# Teensy-Futurlec-Shield_v2.net
KiCad netlist of a schematic drawn in EAGLE
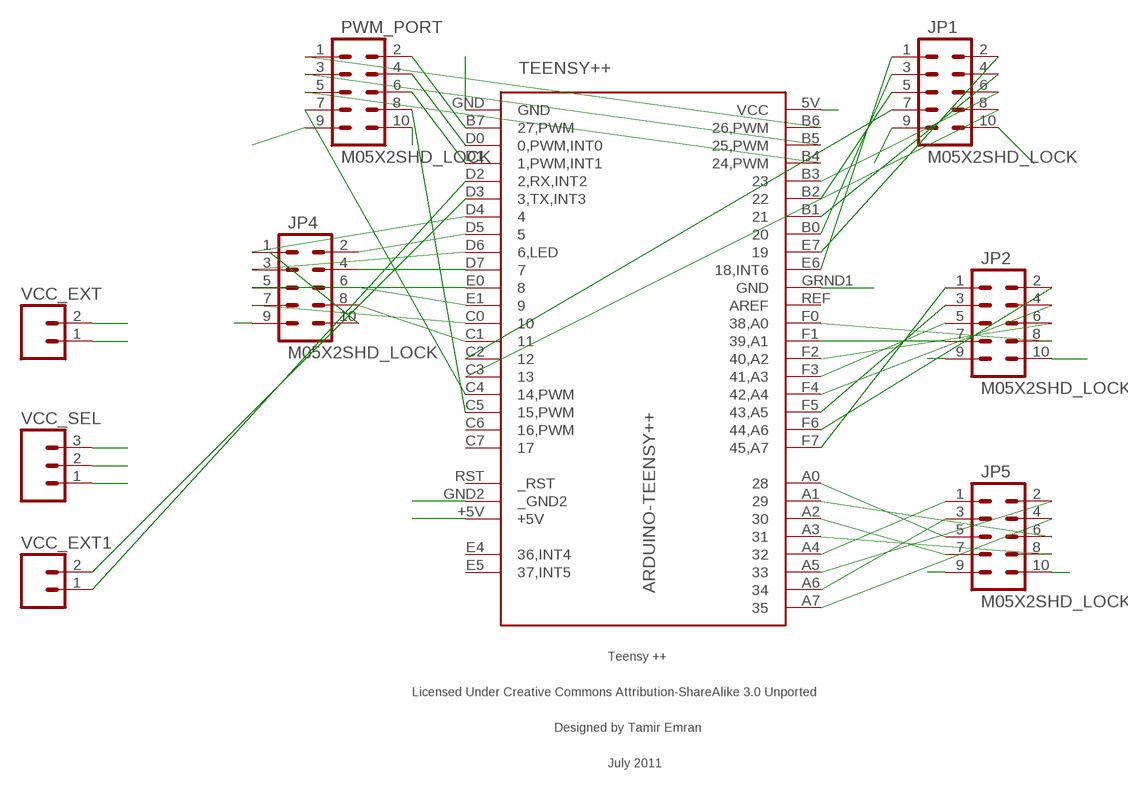
[diagram p0: schematic, sheet 1]

(export (version "E")
  (design (tool "Eeschema 10.0.6"))
  (components
    (comp (ref "JP1")
      (value "M05X2SHD_LOCK")
      (footprint "eagle-import:2X5-SHROUDED_LOCK")
      (libsource (lib "eagle-import") (part "M05X2SHD_LOCK"))
    )
    (comp (ref "JP2")
      (value "M05X2SHD_LOCK")
      (footprint "eagle-import:2X5-SHROUDED_LOCK")
      (libsource (lib "eagle-import") (part "M05X2SHD_LOCK"))
    )
    (comp (ref "JP4")
      (value "M05X2SHD_LOCK")
      (footprint "eagle-import:2X5-SHROUDED_LOCK")
      (libsource (lib "eagle-import") (part "M05X2SHD_LOCK"))
    )
    (comp (ref "JP5")
      (value "M05X2SHD_LOCK")
      (footprint "eagle-import:2X5-SHROUDED_LOCK")
      (libsource (lib "eagle-import") (part "M05X2SHD_LOCK"))
    )
    (comp (ref "PWM_PORT")
      (value "M05X2SHD_LOCK")
      (footprint "eagle-import:2X5-SHROUDED_LOCK")
      (libsource (lib "eagle-import") (part "M05X2SHD_LOCK"))
    )
    (comp (ref "TEENSY++")
      (value "ARDUINO-TEENSY++")
      (footprint "eagle-import:TEENSY++")
      (libsource (lib "eagle-import") (part "ARDUINO-TEENSY++"))
    )
    (comp (ref "VCC_EXT")
      (value "M02POLAR_LOCK")
      (footprint "eagle-import:MOLEX-1X2_LOCK")
      (libsource (lib "eagle-import") (part "M02POLAR_LOCK"))
    )
    (comp (ref "VCC_EXT1")
      (value "M02POLAR_LOCK")
      (footprint "eagle-import:MOLEX-1X2_LOCK")
      (libsource (lib "eagle-import") (part "M02POLAR_LOCK"))
    )
    (comp (ref "VCC_SEL")
      (value "M03PTH")
      (footprint "eagle-import:1X03")
      (libsource (lib "eagle-import") (part "M03PTH"))
    )
  )
  (nets
    (net (code "1") (name "/GND") (class "Default")
      (node (ref "JP1") (pin "10") (pinfunction "10_10") (pintype "passive"))
      (node (ref "JP2") (pin "10") (pinfunction "10_10") (pintype "passive"))
      (node (ref "JP4") (pin "10") (pinfunction "10_10") (pintype "passive"))
      (node (ref "JP5") (pin "10") (pinfunction "10_10") (pintype "passive"))
      (node (ref "PWM_PORT") (pin "10") (pinfunction "10_10") (pintype "passive"))
      (node (ref "TEENSY++") (pin "GND") (pinfunction "GND_GND") (pintype "power_in"))
      (node (ref "TEENSY++") (pin "GND2") (pinfunction "_GND2_GND2") (pintype "power_in"))
      (node (ref "TEENSY++") (pin "GRND1") (pinfunction "GND_GRND1") (pintype "power_in"))
      (node (ref "VCC_EXT") (pin "2") (pinfunction "2_2") (pintype "passive"))
    )
    (net (code "2") (name "/VCC") (class "Default")
      (node (ref "JP1") (pin "9") (pinfunction "9_9") (pintype "passive"))
      (node (ref "JP2") (pin "9") (pinfunction "9_9") (pintype "passive"))
      (node (ref "JP4") (pin "9") (pinfunction "9_9") (pintype "passive"))
      (node (ref "JP5") (pin "9") (pinfunction "9_9") (pintype "passive"))
      (node (ref "PWM_PORT") (pin "9") (pinfunction "9_9") (pintype "passive"))
      (node (ref "VCC_SEL") (pin "2") (pinfunction "2_2") (pintype "passive"))
    )
    (net (code "3") (name "/VCC_EXT") (class "Default")
      (node (ref "VCC_EXT") (pin "1") (pinfunction "1_1") (pintype "passive"))
      (node (ref "VCC_SEL") (pin "3") (pinfunction "3_3") (pintype "passive"))
    )
    (net (code "4") (name "/VCC_TEENSY") (class "Default")
      (node (ref "TEENSY++") (pin "+5V") (pinfunction "+5V_+5V") (pintype "power_in"))
      (node (ref "TEENSY++") (pin "5V") (pinfunction "VCC_5V") (pintype "power_in"))
      (node (ref "VCC_SEL") (pin "1") (pinfunction "1_1") (pintype "passive"))
    )
    (net (code "5") (name "Net-(TEENSY++-0,PWM,INT0)") (class "Default")
      (node (ref "PWM_PORT") (pin "4") (pinfunction "4_4") (pintype "passive"))
      (node (ref "TEENSY++") (pin "D0") (pinfunction "0,PWM,INT0_D0") (pintype "bidirectional"))
    )
    (net (code "6") (name "Net-(TEENSY++-1,PWM,INT1)") (class "Default")
      (node (ref "PWM_PORT") (pin "6") (pinfunction "6_6") (pintype "passive"))
      (node (ref "TEENSY++") (pin "D1") (pinfunction "1,PWM,INT1_D1") (pintype "bidirectional"))
    )
    (net (code "7") (name "Net-(TEENSY++-2,RX,INT2)") (class "Default")
      (node (ref "TEENSY++") (pin "D2") (pinfunction "2,RX,INT2_D2") (pintype "bidirectional"))
      (node (ref "VCC_EXT1") (pin "1") (pinfunction "1_1") (pintype "passive"))
    )
    (net (code "8") (name "Net-(TEENSY++-3,TX,INT3)") (class "Default")
      (node (ref "TEENSY++") (pin "D3") (pinfunction "3,TX,INT3_D3") (pintype "bidirectional"))
      (node (ref "VCC_EXT1") (pin "2") (pinfunction "2_2") (pintype "passive"))
    )
    (net (code "9") (name "Net-(TEENSY++-4)") (class "Default")
      (node (ref "JP4") (pin "1") (pinfunction "1_1") (pintype "passive"))
      (node (ref "TEENSY++") (pin "D4") (pinfunction "4_D4") (pintype "bidirectional"))
    )
    (net (code "10") (name "Net-(TEENSY++-5)") (class "Default")
      (node (ref "JP4") (pin "2") (pinfunction "2_2") (pintype "passive"))
      (node (ref "TEENSY++") (pin "D5") (pinfunction "5_D5") (pintype "bidirectional"))
    )
    (net (code "11") (name "Net-(TEENSY++-6,LED)") (class "Default")
      (node (ref "JP4") (pin "3") (pinfunction "3_3") (pintype "passive"))
      (node (ref "TEENSY++") (pin "D6") (pinfunction "6,LED_D6") (pintype "bidirectional"))
    )
    (net (code "12") (name "Net-(TEENSY++-7)") (class "Default")
      (node (ref "JP4") (pin "4") (pinfunction "4_4") (pintype "passive"))
      (node (ref "TEENSY++") (pin "D7") (pinfunction "7_D7") (pintype "bidirectional"))
    )
    (net (code "13") (name "Net-(TEENSY++-8)") (class "Default")
      (node (ref "JP4") (pin "5") (pinfunction "5_5") (pintype "passive"))
      (node (ref "TEENSY++") (pin "E0") (pinfunction "8_E0") (pintype "bidirectional"))
    )
    (net (code "14") (name "Net-(TEENSY++-9)") (class "Default")
      (node (ref "JP4") (pin "6") (pinfunction "6_6") (pintype "passive"))
      (node (ref "TEENSY++") (pin "E1") (pinfunction "9_E1") (pintype "bidirectional"))
    )
    (net (code "15") (name "Net-(TEENSY++-10)") (class "Default")
      (node (ref "JP4") (pin "7") (pinfunction "7_7") (pintype "passive"))
      (node (ref "TEENSY++") (pin "C0") (pinfunction "10_C0") (pintype "bidirectional"))
    )
    (net (code "16") (name "Net-(TEENSY++-11)") (class "Default")
      (node (ref "JP4") (pin "8") (pinfunction "8_8") (pintype "passive"))
      (node (ref "TEENSY++") (pin "C1") (pinfunction "11_C1") (pintype "bidirectional"))
    )
    (net (code "17") (name "Net-(TEENSY++-12)") (class "Default")
      (node (ref "JP1") (pin "7") (pinfunction "7_7") (pintype "passive"))
      (node (ref "TEENSY++") (pin "C2") (pinfunction "12_C2") (pintype "bidirectional"))
    )
    (net (code "18") (name "Net-(TEENSY++-13)") (class "Default")
      (node (ref "JP1") (pin "8") (pinfunction "8_8") (pintype "passive"))
      (node (ref "TEENSY++") (pin "C3") (pinfunction "13_C3") (pintype "bidirectional"))
    )
    (net (code "19") (name "Net-(TEENSY++-14,PWM)") (class "Default")
      (node (ref "PWM_PORT") (pin "7") (pinfunction "7_7") (pintype "passive"))
      (node (ref "TEENSY++") (pin "C4") (pinfunction "14,PWM_C4") (pintype "bidirectional"))
    )
    (net (code "20") (name "Net-(TEENSY++-15,PWM)") (class "Default")
      (node (ref "PWM_PORT") (pin "8") (pinfunction "8_8") (pintype "passive"))
      (node (ref "TEENSY++") (pin "C5") (pinfunction "15,PWM_C5") (pintype "bidirectional"))
    )
    (net (code "21") (name "Net-(TEENSY++-18,INT6)") (class "Default")
      (node (ref "JP1") (pin "1") (pinfunction "1_1") (pintype "passive"))
      (node (ref "TEENSY++") (pin "E6") (pinfunction "18,INT6_E6") (pintype "bidirectional"))
    )
    (net (code "22") (name "Net-(TEENSY++-19)") (class "Default")
      (node (ref "JP1") (pin "2") (pinfunction "2_2") (pintype "passive"))
      (node (ref "TEENSY++") (pin "E7") (pinfunction "19_E7") (pintype "bidirectional"))
    )
    (net (code "23") (name "Net-(TEENSY++-20)") (class "Default")
      (node (ref "JP1") (pin "3") (pinfunction "3_3") (pintype "passive"))
      (node (ref "TEENSY++") (pin "B0") (pinfunction "20_B0") (pintype "bidirectional"))
    )
    (net (code "24") (name "Net-(TEENSY++-21)") (class "Default")
      (node (ref "JP1") (pin "4") (pinfunction "4_4") (pintype "passive"))
      (node (ref "TEENSY++") (pin "B1") (pinfunction "21_B1") (pintype "bidirectional"))
    )
    (net (code "25") (name "Net-(TEENSY++-22)") (class "Default")
      (node (ref "JP1") (pin "5") (pinfunction "5_5") (pintype "passive"))
      (node (ref "TEENSY++") (pin "B2") (pinfunction "22_B2") (pintype "bidirectional"))
    )
    (net (code "26") (name "Net-(TEENSY++-23)") (class "Default")
      (node (ref "JP1") (pin "6") (pinfunction "6_6") (pintype "passive"))
      (node (ref "TEENSY++") (pin "B3") (pinfunction "23_B3") (pintype "bidirectional"))
    )
    (net (code "27") (name "Net-(TEENSY++-24,PWM)") (class "Default")
      (node (ref "PWM_PORT") (pin "5") (pinfunction "5_5") (pintype "passive"))
      (node (ref "TEENSY++") (pin "B4") (pinfunction "24,PWM_B4") (pintype "bidirectional"))
    )
    (net (code "28") (name "Net-(TEENSY++-25,PWM)") (class "Default")
      (node (ref "PWM_PORT") (pin "3") (pinfunction "3_3") (pintype "passive"))
      (node (ref "TEENSY++") (pin "B5") (pinfunction "25,PWM_B5") (pintype "bidirectional"))
    )
    (net (code "29") (name "Net-(TEENSY++-26,PWM)") (class "Default")
      (node (ref "PWM_PORT") (pin "1") (pinfunction "1_1") (pintype "passive"))
      (node (ref "TEENSY++") (pin "B6") (pinfunction "26,PWM_B6") (pintype "bidirectional"))
    )
    (net (code "30") (name "Net-(TEENSY++-27,PWM)") (class "Default")
      (node (ref "PWM_PORT") (pin "2") (pinfunction "2_2") (pintype "passive"))
      (node (ref "TEENSY++") (pin "B7") (pinfunction "27,PWM_B7") (pintype "bidirectional"))
    )
    (net (code "31") (name "Net-(TEENSY++-28)") (class "Default")
      (node (ref "JP5") (pin "5") (pinfunction "5_5") (pintype "passive"))
      (node (ref "TEENSY++") (pin "A0") (pinfunction "28_A0") (pintype "bidirectional"))
    )
    (net (code "32") (name "Net-(TEENSY++-29)") (class "Default")
      (node (ref "JP5") (pin "6") (pinfunction "6_6") (pintype "passive"))
      (node (ref "TEENSY++") (pin "A1") (pinfunction "29_A1") (pintype "bidirectional"))
    )
    (net (code "33") (name "Net-(TEENSY++-30)") (class "Default")
      (node (ref "JP5") (pin "7") (pinfunction "7_7") (pintype "passive"))
      (node (ref "TEENSY++") (pin "A2") (pinfunction "30_A2") (pintype "bidirectional"))
    )
    (net (code "34") (name "Net-(TEENSY++-31)") (class "Default")
      (node (ref "JP5") (pin "8") (pinfunction "8_8") (pintype "passive"))
      (node (ref "TEENSY++") (pin "A3") (pinfunction "31_A3") (pintype "bidirectional"))
    )
    (net (code "35") (name "Net-(TEENSY++-32)") (class "Default")
      (node (ref "JP5") (pin "1") (pinfunction "1_1") (pintype "passive"))
      (node (ref "TEENSY++") (pin "A4") (pinfunction "32_A4") (pintype "bidirectional"))
    )
    (net (code "36") (name "Net-(TEENSY++-33)") (class "Default")
      (node (ref "JP5") (pin "2") (pinfunction "2_2") (pintype "passive"))
      (node (ref "TEENSY++") (pin "A5") (pinfunction "33_A5") (pintype "bidirectional"))
    )
    (net (code "37") (name "Net-(TEENSY++-34)") (class "Default")
      (node (ref "JP5") (pin "3") (pinfunction "3_3") (pintype "passive"))
      (node (ref "TEENSY++") (pin "A6") (pinfunction "34_A6") (pintype "bidirectional"))
    )
    (net (code "38") (name "Net-(TEENSY++-35)") (class "Default")
      (node (ref "JP5") (pin "4") (pinfunction "4_4") (pintype "passive"))
      (node (ref "TEENSY++") (pin "A7") (pinfunction "35_A7") (pintype "bidirectional"))
    )
    (net (code "39") (name "Net-(TEENSY++-38,A0)") (class "Default")
      (node (ref "JP2") (pin "8") (pinfunction "8_8") (pintype "passive"))
      (node (ref "TEENSY++") (pin "F0") (pinfunction "38,A0_F0") (pintype "bidirectional"))
    )
    (net (code "40") (name "Net-(TEENSY++-39,A1)") (class "Default")
      (node (ref "JP2") (pin "7") (pinfunction "7_7") (pintype "passive"))
      (node (ref "TEENSY++") (pin "F1") (pinfunction "39,A1_F1") (pintype "bidirectional"))
    )
    (net (code "41") (name "Net-(TEENSY++-40,A2)") (class "Default")
      (node (ref "JP2") (pin "6") (pinfunction "6_6") (pintype "passive"))
      (node (ref "TEENSY++") (pin "F2") (pinfunction "40,A2_F2") (pintype "bidirectional"))
    )
    (net (code "42") (name "Net-(TEENSY++-41,A3)") (class "Default")
      (node (ref "JP2") (pin "5") (pinfunction "5_5") (pintype "passive"))
      (node (ref "TEENSY++") (pin "F3") (pinfunction "41,A3_F3") (pintype "bidirectional"))
    )
    (net (code "43") (name "Net-(TEENSY++-42,A4)") (class "Default")
      (node (ref "JP2") (pin "4") (pinfunction "4_4") (pintype "passive"))
      (node (ref "TEENSY++") (pin "F4") (pinfunction "42,A4_F4") (pintype "bidirectional"))
    )
    (net (code "44") (name "Net-(TEENSY++-43,A5)") (class "Default")
      (node (ref "JP2") (pin "3") (pinfunction "3_3") (pintype "passive"))
      (node (ref "TEENSY++") (pin "F5") (pinfunction "43,A5_F5") (pintype "bidirectional"))
    )
    (net (code "45") (name "Net-(TEENSY++-44,A6)") (class "Default")
      (node (ref "JP2") (pin "2") (pinfunction "2_2") (pintype "passive"))
      (node (ref "TEENSY++") (pin "F6") (pinfunction "44,A6_F6") (pintype "bidirectional"))
    )
    (net (code "46") (name "Net-(TEENSY++-45,A7)") (class "Default")
      (node (ref "JP2") (pin "1") (pinfunction "1_1") (pintype "passive"))
      (node (ref "TEENSY++") (pin "F7") (pinfunction "45,A7_F7") (pintype "bidirectional"))
    )
    (net (code "47") (name "unconnected-(TEENSY++-16,PWM-PadC6)") (class "Default")
      (node (ref "TEENSY++") (pin "C6") (pinfunction "16,PWM_C6") (pintype "bidirectional"))
    )
    (net (code "48") (name "unconnected-(TEENSY++-17-PadC7)") (class "Default")
      (node (ref "TEENSY++") (pin "C7") (pinfunction "17_C7") (pintype "bidirectional"))
    )
    (net (code "49") (name "unconnected-(TEENSY++-36,INT4-PadE4)") (class "Default")
      (node (ref "TEENSY++") (pin "E4") (pinfunction "36,INT4_E4") (pintype "bidirectional"))
    )
    (net (code "50") (name "unconnected-(TEENSY++-37,INT5-PadE5)") (class "Default")
      (node (ref "TEENSY++") (pin "E5") (pinfunction "37,INT5_E5") (pintype "bidirectional"))
    )
    (net (code "51") (name "unconnected-(TEENSY++-AREF-PadREF)") (class "Default")
      (node (ref "TEENSY++") (pin "REF") (pinfunction "AREF_REF") (pintype "input"))
    )
    (net (code "52") (name "unconnected-(TEENSY++-_RST-PadRST)") (class "Default")
      (node (ref "TEENSY++") (pin "RST") (pinfunction "_RST_RST") (pintype "input"))
    )
  )
)
